# Automaton_no_switches.net
KiCad netlist of a schematic drawn in EAGLE
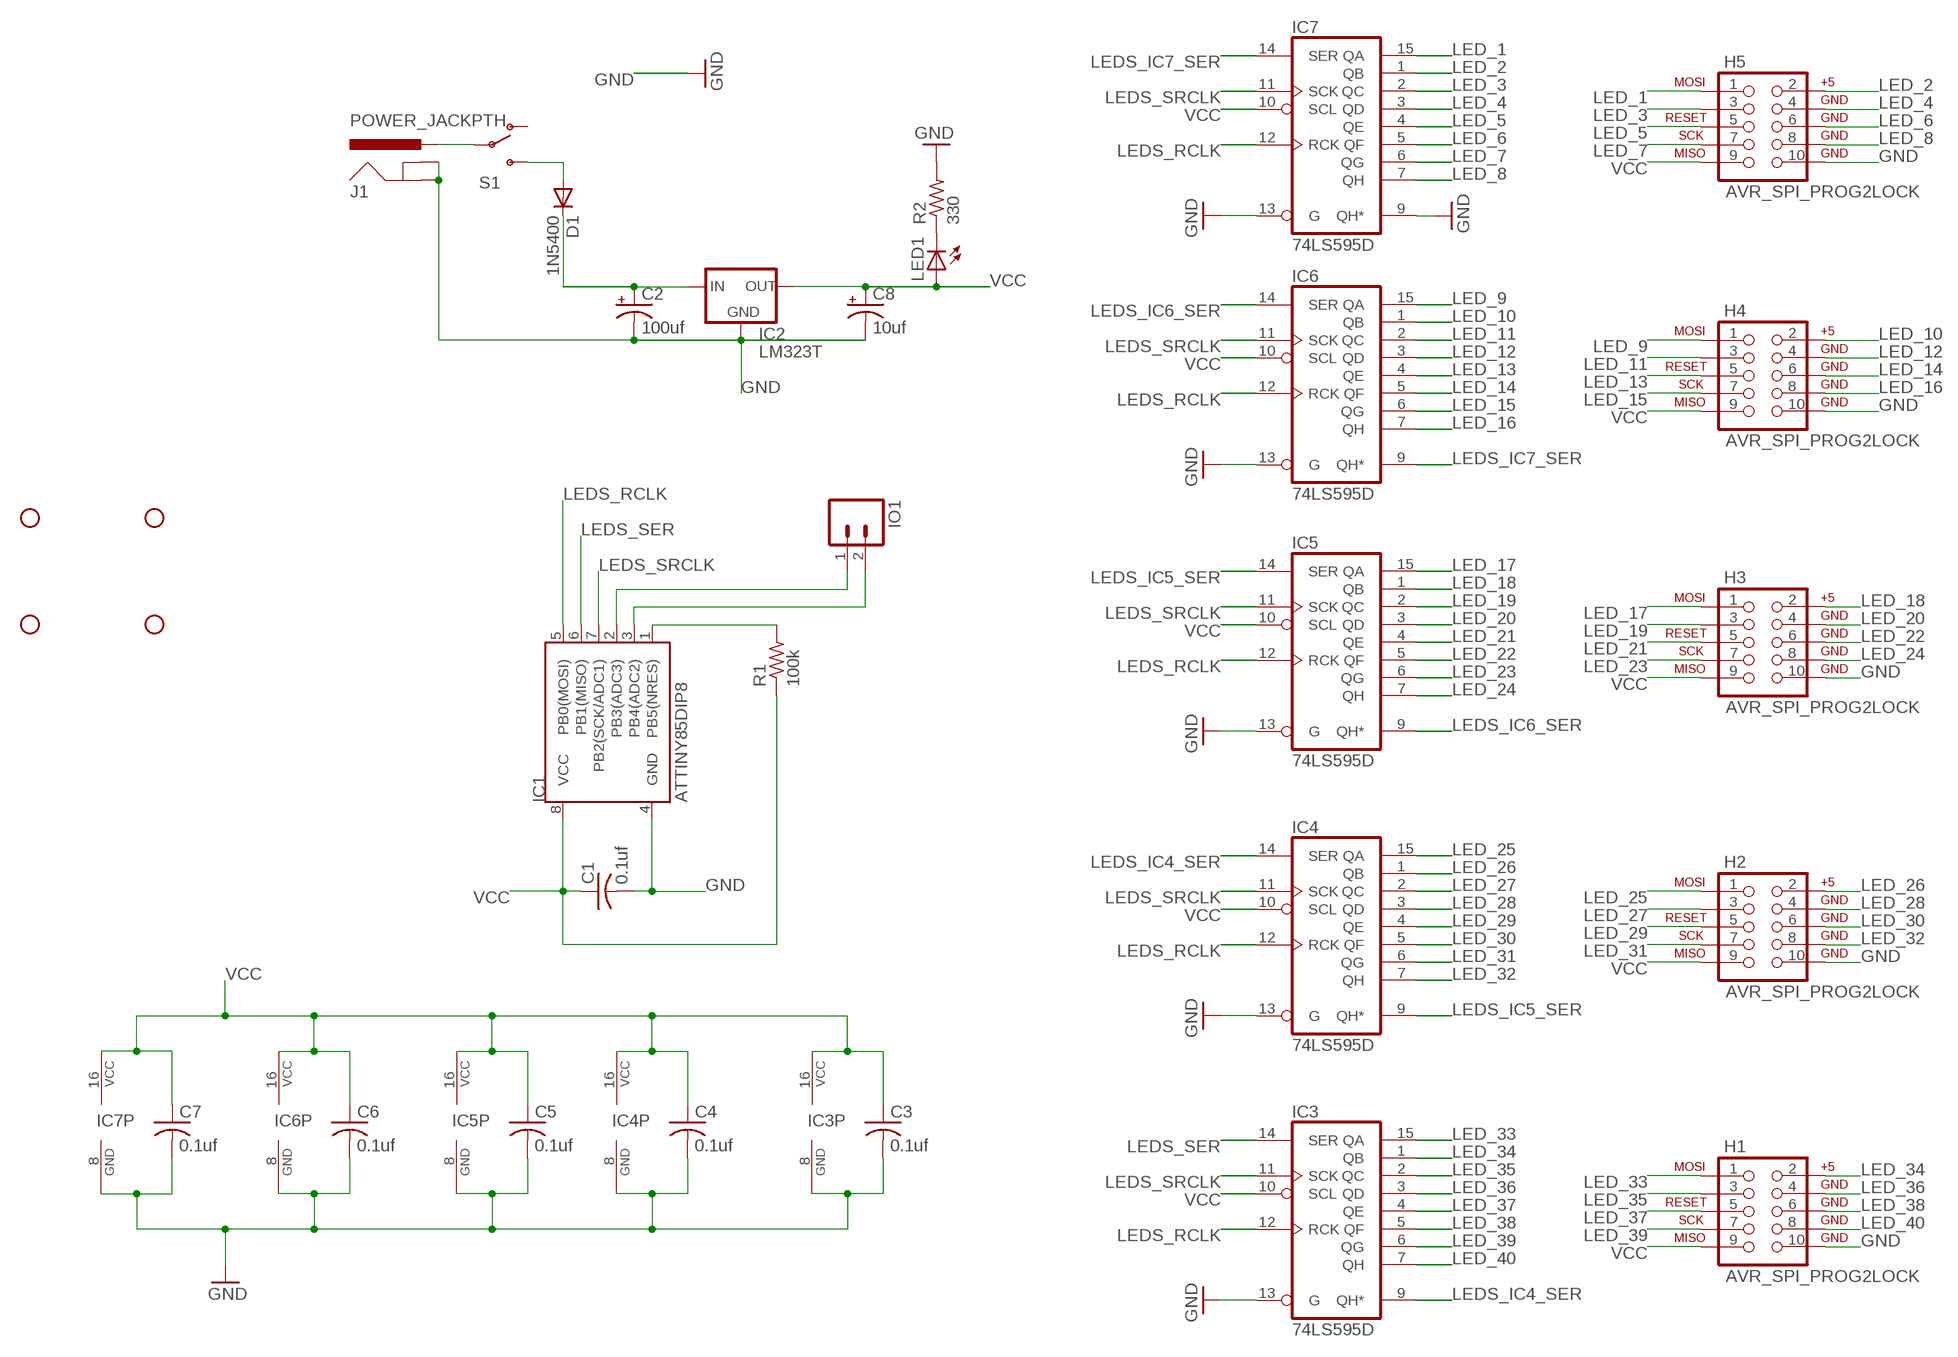
[diagram p0: schematic, sheet 1]

(export (version "E")
  (design (tool "Eeschema 10.0.6"))
  (components
    (comp (ref "C1")
      (value "0.1uf")
      (footprint "eagle-import:C1206")
      (libsource (lib "eagle-import") (part "C-USC1206"))
    )
    (comp (ref "C2")
      (value "100uf")
      (footprint "eagle-import:E5-10,5")
      (libsource (lib "eagle-import") (part "CPOL-USE5-10.5"))
    )
    (comp (ref "C3")
      (value "0.1uf")
      (footprint "eagle-import:C1206")
      (libsource (lib "eagle-import") (part "C-USC1206"))
    )
    (comp (ref "C4")
      (value "0.1uf")
      (footprint "eagle-import:C1206")
      (libsource (lib "eagle-import") (part "C-USC1206"))
    )
    (comp (ref "C5")
      (value "0.1uf")
      (footprint "eagle-import:C1206")
      (libsource (lib "eagle-import") (part "C-USC1206"))
    )
    (comp (ref "C6")
      (value "0.1uf")
      (footprint "eagle-import:C1206")
      (libsource (lib "eagle-import") (part "C-USC1206"))
    )
    (comp (ref "C7")
      (value "0.1uf")
      (footprint "eagle-import:C1206")
      (libsource (lib "eagle-import") (part "C-USC1206"))
    )
    (comp (ref "C8")
      (value "10uf")
      (footprint "eagle-import:E2-5")
      (libsource (lib "eagle-import") (part "CPOL-USE2-5"))
    )
    (comp (ref "D1")
      (value "1N5400")
      (footprint "eagle-import:DO201-15")
      (libsource (lib "eagle-import") (part "1N5400"))
    )
    (comp (ref "H1")
      (value "AVR_SPI_PROG2LOCK")
      (footprint "eagle-import:2X5-SHROUDED_LOCK")
      (libsource (lib "eagle-import") (part "AVR_SPI_PROG2LOCK"))
    )
    (comp (ref "H2")
      (value "AVR_SPI_PROG2LOCK")
      (footprint "eagle-import:2X5-SHROUDED_LOCK")
      (libsource (lib "eagle-import") (part "AVR_SPI_PROG2LOCK"))
    )
    (comp (ref "H3")
      (value "AVR_SPI_PROG2LOCK")
      (footprint "eagle-import:2X5-SHROUDED_LOCK")
      (libsource (lib "eagle-import") (part "AVR_SPI_PROG2LOCK"))
    )
    (comp (ref "H4")
      (value "AVR_SPI_PROG2LOCK")
      (footprint "eagle-import:2X5-SHROUDED_LOCK")
      (libsource (lib "eagle-import") (part "AVR_SPI_PROG2LOCK"))
    )
    (comp (ref "H5")
      (value "AVR_SPI_PROG2LOCK")
      (footprint "eagle-import:2X5-SHROUDED_LOCK")
      (libsource (lib "eagle-import") (part "AVR_SPI_PROG2LOCK"))
    )
    (comp (ref "HOLE1")
      (value "STAND-OFF")
      (footprint "eagle-import:STAND-OFF")
      (libsource (lib "eagle-import") (part "STAND-OFF"))
    )
    (comp (ref "HOLE2")
      (value "STAND-OFF")
      (footprint "eagle-import:STAND-OFF")
      (libsource (lib "eagle-import") (part "STAND-OFF"))
    )
    (comp (ref "HOLE3")
      (value "STAND-OFF")
      (footprint "eagle-import:STAND-OFF")
      (libsource (lib "eagle-import") (part "STAND-OFF"))
    )
    (comp (ref "HOLE4")
      (value "STAND-OFF")
      (footprint "eagle-import:STAND-OFF")
      (libsource (lib "eagle-import") (part "STAND-OFF"))
    )
    (comp (ref "IC1")
      (value "ATTINY85DIP8")
      (footprint "eagle-import:DIP08")
      (libsource (lib "eagle-import") (part "ATTINY85DIP8"))
    )
    (comp (ref "IC2")
      (value "LM323T")
      (footprint "eagle-import:TO220-IGO")
      (libsource (lib "eagle-import") (part "V_REG_78XXSINK"))
    )
    (comp (ref "IC3")
      (value "74LS595D")
      (footprint "eagle-import:SO16")
      (libsource (lib "eagle-import") (part "74595DLS"))
    )
    (comp (ref "IC4")
      (value "74LS595D")
      (footprint "eagle-import:SO16")
      (libsource (lib "eagle-import") (part "74595DLS"))
    )
    (comp (ref "IC5")
      (value "74LS595D")
      (footprint "eagle-import:SO16")
      (libsource (lib "eagle-import") (part "74595DLS"))
    )
    (comp (ref "IC6")
      (value "74LS595D")
      (footprint "eagle-import:SO16")
      (libsource (lib "eagle-import") (part "74595DLS"))
    )
    (comp (ref "IC7")
      (value "74LS595D")
      (footprint "eagle-import:SO16")
      (libsource (lib "eagle-import") (part "74595DLS"))
    )
    (comp (ref "IO1")
      (value "M02PTH3")
      (footprint "eagle-import:1X02_LONGPADS")
      (libsource (lib "eagle-import") (part "M02PTH3"))
    )
    (comp (ref "J1")
      (value "POWER_JACKPTH")
      (footprint "eagle-import:POWER_JACK_PTH")
      (libsource (lib "eagle-import") (part "POWER_JACKPTH"))
    )
    (comp (ref "LED1")
      (value "LEDSMT1206")
      (footprint "eagle-import:1206")
      (libsource (lib "eagle-import") (part "LEDSMT1206"))
    )
    (comp (ref "R1")
      (value "100k")
      (footprint "eagle-import:M1206")
      (libsource (lib "eagle-import") (part "R-US_M1206"))
    )
    (comp (ref "R2")
      (value "330")
      (footprint "eagle-import:M1206")
      (libsource (lib "eagle-import") (part "R-US_M1206"))
    )
    (comp (ref "S1")
      (value "SWITCH-SPDTPTH_LOCK")
      (footprint "eagle-import:SWITCH-SPDT_LOCK.007S")
      (libsource (lib "eagle-import") (part "SWITCH-SPDTPTH_LOCK"))
    )
  )
  (nets
    (net (code "1") (name "/LEDS_IC4_SER") (class "Default")
      (node (ref "IC3") (pin "9") (pinfunction "QH*_9") (pintype "tri_state"))
      (node (ref "IC4") (pin "14") (pinfunction "SER_14") (pintype "input"))
    )
    (net (code "2") (name "/LEDS_IC5_SER") (class "Default")
      (node (ref "IC4") (pin "9") (pinfunction "QH*_9") (pintype "tri_state"))
      (node (ref "IC5") (pin "14") (pinfunction "SER_14") (pintype "input"))
    )
    (net (code "3") (name "/LEDS_IC6_SER") (class "Default")
      (node (ref "IC5") (pin "9") (pinfunction "QH*_9") (pintype "tri_state"))
      (node (ref "IC6") (pin "14") (pinfunction "SER_14") (pintype "input"))
    )
    (net (code "4") (name "/LEDS_IC7_SER") (class "Default")
      (node (ref "IC6") (pin "9") (pinfunction "QH*_9") (pintype "tri_state"))
      (node (ref "IC7") (pin "14") (pinfunction "SER_14") (pintype "input"))
    )
    (net (code "5") (name "/LEDS_RCLK") (class "Default")
      (node (ref "IC1") (pin "5") (pinfunction "PB0(MOSI)_5") (pintype "bidirectional"))
      (node (ref "IC3") (pin "12") (pinfunction "RCK_12") (pintype "input"))
      (node (ref "IC4") (pin "12") (pinfunction "RCK_12") (pintype "input"))
      (node (ref "IC5") (pin "12") (pinfunction "RCK_12") (pintype "input"))
      (node (ref "IC6") (pin "12") (pinfunction "RCK_12") (pintype "input"))
      (node (ref "IC7") (pin "12") (pinfunction "RCK_12") (pintype "input"))
    )
    (net (code "6") (name "/LEDS_SER") (class "Default")
      (node (ref "IC1") (pin "6") (pinfunction "PB1(MISO)_6") (pintype "bidirectional"))
      (node (ref "IC3") (pin "14") (pinfunction "SER_14") (pintype "input"))
    )
    (net (code "7") (name "/LEDS_SRCLK") (class "Default")
      (node (ref "IC1") (pin "7") (pinfunction "PB2(SCK/ADC1)_7") (pintype "bidirectional"))
      (node (ref "IC3") (pin "11") (pinfunction "SCK_11") (pintype "input"))
      (node (ref "IC4") (pin "11") (pinfunction "SCK_11") (pintype "input"))
      (node (ref "IC5") (pin "11") (pinfunction "SCK_11") (pintype "input"))
      (node (ref "IC6") (pin "11") (pinfunction "SCK_11") (pintype "input"))
      (node (ref "IC7") (pin "11") (pinfunction "SCK_11") (pintype "input"))
    )
    (net (code "8") (name "/LED_1") (class "Default")
      (node (ref "H5") (pin "1") (pinfunction "1_1") (pintype "passive"))
      (node (ref "IC7") (pin "15") (pinfunction "QA_15") (pintype "tri_state"))
    )
    (net (code "9") (name "/LED_2") (class "Default")
      (node (ref "H5") (pin "2") (pinfunction "2_2") (pintype "passive"))
      (node (ref "IC7") (pin "1") (pinfunction "QB_1") (pintype "tri_state"))
    )
    (net (code "10") (name "/LED_3") (class "Default")
      (node (ref "H5") (pin "3") (pinfunction "3_3") (pintype "passive"))
      (node (ref "IC7") (pin "2") (pinfunction "QC_2") (pintype "tri_state"))
    )
    (net (code "11") (name "/LED_4") (class "Default")
      (node (ref "H5") (pin "4") (pinfunction "4_4") (pintype "passive"))
      (node (ref "IC7") (pin "3") (pinfunction "QD_3") (pintype "tri_state"))
    )
    (net (code "12") (name "/LED_5") (class "Default")
      (node (ref "H5") (pin "5") (pinfunction "5_5") (pintype "passive"))
      (node (ref "IC7") (pin "4") (pinfunction "QE_4") (pintype "tri_state"))
    )
    (net (code "13") (name "/LED_6") (class "Default")
      (node (ref "H5") (pin "6") (pinfunction "6_6") (pintype "passive"))
      (node (ref "IC7") (pin "5") (pinfunction "QF_5") (pintype "tri_state"))
    )
    (net (code "14") (name "/LED_7") (class "Default")
      (node (ref "H5") (pin "7") (pinfunction "7_7") (pintype "passive"))
      (node (ref "IC7") (pin "6") (pinfunction "QG_6") (pintype "tri_state"))
    )
    (net (code "15") (name "/LED_8") (class "Default")
      (node (ref "H5") (pin "8") (pinfunction "8_8") (pintype "passive"))
      (node (ref "IC7") (pin "7") (pinfunction "QH_7") (pintype "tri_state"))
    )
    (net (code "16") (name "/LED_9") (class "Default")
      (node (ref "H4") (pin "1") (pinfunction "1_1") (pintype "passive"))
      (node (ref "IC6") (pin "15") (pinfunction "QA_15") (pintype "tri_state"))
    )
    (net (code "17") (name "/LED_10") (class "Default")
      (node (ref "H4") (pin "2") (pinfunction "2_2") (pintype "passive"))
      (node (ref "IC6") (pin "1") (pinfunction "QB_1") (pintype "tri_state"))
    )
    (net (code "18") (name "/LED_11") (class "Default")
      (node (ref "H4") (pin "3") (pinfunction "3_3") (pintype "passive"))
      (node (ref "IC6") (pin "2") (pinfunction "QC_2") (pintype "tri_state"))
    )
    (net (code "19") (name "/LED_12") (class "Default")
      (node (ref "H4") (pin "4") (pinfunction "4_4") (pintype "passive"))
      (node (ref "IC6") (pin "3") (pinfunction "QD_3") (pintype "tri_state"))
    )
    (net (code "20") (name "/LED_13") (class "Default")
      (node (ref "H4") (pin "5") (pinfunction "5_5") (pintype "passive"))
      (node (ref "IC6") (pin "4") (pinfunction "QE_4") (pintype "tri_state"))
    )
    (net (code "21") (name "/LED_14") (class "Default")
      (node (ref "H4") (pin "6") (pinfunction "6_6") (pintype "passive"))
      (node (ref "IC6") (pin "5") (pinfunction "QF_5") (pintype "tri_state"))
    )
    (net (code "22") (name "/LED_15") (class "Default")
      (node (ref "H4") (pin "7") (pinfunction "7_7") (pintype "passive"))
      (node (ref "IC6") (pin "6") (pinfunction "QG_6") (pintype "tri_state"))
    )
    (net (code "23") (name "/LED_16") (class "Default")
      (node (ref "H4") (pin "8") (pinfunction "8_8") (pintype "passive"))
      (node (ref "IC6") (pin "7") (pinfunction "QH_7") (pintype "tri_state"))
    )
    (net (code "24") (name "/LED_17") (class "Default")
      (node (ref "H3") (pin "1") (pinfunction "1_1") (pintype "passive"))
      (node (ref "IC5") (pin "15") (pinfunction "QA_15") (pintype "tri_state"))
    )
    (net (code "25") (name "/LED_18") (class "Default")
      (node (ref "H3") (pin "2") (pinfunction "2_2") (pintype "passive"))
      (node (ref "IC5") (pin "1") (pinfunction "QB_1") (pintype "tri_state"))
    )
    (net (code "26") (name "/LED_19") (class "Default")
      (node (ref "H3") (pin "3") (pinfunction "3_3") (pintype "passive"))
      (node (ref "IC5") (pin "2") (pinfunction "QC_2") (pintype "tri_state"))
    )
    (net (code "27") (name "/LED_20") (class "Default")
      (node (ref "H3") (pin "4") (pinfunction "4_4") (pintype "passive"))
      (node (ref "IC5") (pin "3") (pinfunction "QD_3") (pintype "tri_state"))
    )
    (net (code "28") (name "/LED_21") (class "Default")
      (node (ref "H3") (pin "5") (pinfunction "5_5") (pintype "passive"))
      (node (ref "IC5") (pin "4") (pinfunction "QE_4") (pintype "tri_state"))
    )
    (net (code "29") (name "/LED_22") (class "Default")
      (node (ref "H3") (pin "6") (pinfunction "6_6") (pintype "passive"))
      (node (ref "IC5") (pin "5") (pinfunction "QF_5") (pintype "tri_state"))
    )
    (net (code "30") (name "/LED_23") (class "Default")
      (node (ref "H3") (pin "7") (pinfunction "7_7") (pintype "passive"))
      (node (ref "IC5") (pin "6") (pinfunction "QG_6") (pintype "tri_state"))
    )
    (net (code "31") (name "/LED_24") (class "Default")
      (node (ref "H3") (pin "8") (pinfunction "8_8") (pintype "passive"))
      (node (ref "IC5") (pin "7") (pinfunction "QH_7") (pintype "tri_state"))
    )
    (net (code "32") (name "/LED_25") (class "Default")
      (node (ref "H2") (pin "1") (pinfunction "1_1") (pintype "passive"))
      (node (ref "IC4") (pin "15") (pinfunction "QA_15") (pintype "tri_state"))
    )
    (net (code "33") (name "/LED_26") (class "Default")
      (node (ref "H2") (pin "2") (pinfunction "2_2") (pintype "passive"))
      (node (ref "IC4") (pin "1") (pinfunction "QB_1") (pintype "tri_state"))
    )
    (net (code "34") (name "/LED_27") (class "Default")
      (node (ref "H2") (pin "3") (pinfunction "3_3") (pintype "passive"))
      (node (ref "IC4") (pin "2") (pinfunction "QC_2") (pintype "tri_state"))
    )
    (net (code "35") (name "/LED_28") (class "Default")
      (node (ref "H2") (pin "4") (pinfunction "4_4") (pintype "passive"))
      (node (ref "IC4") (pin "3") (pinfunction "QD_3") (pintype "tri_state"))
    )
    (net (code "36") (name "/LED_29") (class "Default")
      (node (ref "H2") (pin "5") (pinfunction "5_5") (pintype "passive"))
      (node (ref "IC4") (pin "4") (pinfunction "QE_4") (pintype "tri_state"))
    )
    (net (code "37") (name "/LED_30") (class "Default")
      (node (ref "H2") (pin "6") (pinfunction "6_6") (pintype "passive"))
      (node (ref "IC4") (pin "5") (pinfunction "QF_5") (pintype "tri_state"))
    )
    (net (code "38") (name "/LED_31") (class "Default")
      (node (ref "H2") (pin "7") (pinfunction "7_7") (pintype "passive"))
      (node (ref "IC4") (pin "6") (pinfunction "QG_6") (pintype "tri_state"))
    )
    (net (code "39") (name "/LED_32") (class "Default")
      (node (ref "H2") (pin "8") (pinfunction "8_8") (pintype "passive"))
      (node (ref "IC4") (pin "7") (pinfunction "QH_7") (pintype "tri_state"))
    )
    (net (code "40") (name "/LED_33") (class "Default")
      (node (ref "H1") (pin "1") (pinfunction "1_1") (pintype "passive"))
      (node (ref "IC3") (pin "15") (pinfunction "QA_15") (pintype "tri_state"))
    )
    (net (code "41") (name "/LED_34") (class "Default")
      (node (ref "H1") (pin "2") (pinfunction "2_2") (pintype "passive"))
      (node (ref "IC3") (pin "1") (pinfunction "QB_1") (pintype "tri_state"))
    )
    (net (code "42") (name "/LED_35") (class "Default")
      (node (ref "H1") (pin "3") (pinfunction "3_3") (pintype "passive"))
      (node (ref "IC3") (pin "2") (pinfunction "QC_2") (pintype "tri_state"))
    )
    (net (code "43") (name "/LED_36") (class "Default")
      (node (ref "H1") (pin "4") (pinfunction "4_4") (pintype "passive"))
      (node (ref "IC3") (pin "3") (pinfunction "QD_3") (pintype "tri_state"))
    )
    (net (code "44") (name "/LED_37") (class "Default")
      (node (ref "H1") (pin "5") (pinfunction "5_5") (pintype "passive"))
      (node (ref "IC3") (pin "4") (pinfunction "QE_4") (pintype "tri_state"))
    )
    (net (code "45") (name "/LED_38") (class "Default")
      (node (ref "H1") (pin "6") (pinfunction "6_6") (pintype "passive"))
      (node (ref "IC3") (pin "5") (pinfunction "QF_5") (pintype "tri_state"))
    )
    (net (code "46") (name "/LED_39") (class "Default")
      (node (ref "H1") (pin "7") (pinfunction "7_7") (pintype "passive"))
      (node (ref "IC3") (pin "6") (pinfunction "QG_6") (pintype "tri_state"))
    )
    (net (code "47") (name "/LED_40") (class "Default")
      (node (ref "H1") (pin "8") (pinfunction "8_8") (pintype "passive"))
      (node (ref "IC3") (pin "7") (pinfunction "QH_7") (pintype "tri_state"))
    )
    (net (code "48") (name "/VCC") (class "Default")
      (node (ref "C1") (pin "1") (pinfunction "1_1") (pintype "passive"))
      (node (ref "C3") (pin "1") (pinfunction "1_1") (pintype "passive"))
      (node (ref "C4") (pin "1") (pinfunction "1_1") (pintype "passive"))
      (node (ref "C5") (pin "1") (pinfunction "1_1") (pintype "passive"))
      (node (ref "C6") (pin "1") (pinfunction "1_1") (pintype "passive"))
      (node (ref "C7") (pin "1") (pinfunction "1_1") (pintype "passive"))
      (node (ref "C8") (pin "+") (pinfunction "+_+") (pintype "passive"))
      (node (ref "H1") (pin "9") (pinfunction "9_9") (pintype "passive"))
      (node (ref "H2") (pin "9") (pinfunction "9_9") (pintype "passive"))
      (node (ref "H3") (pin "9") (pinfunction "9_9") (pintype "passive"))
      (node (ref "H4") (pin "9") (pinfunction "9_9") (pintype "passive"))
      (node (ref "H5") (pin "9") (pinfunction "9_9") (pintype "passive"))
      (node (ref "IC1") (pin "8") (pinfunction "VCC_8") (pintype "bidirectional"))
      (node (ref "IC2") (pin "OUT") (pinfunction "OUT_OUT") (pintype "output"))
      (node (ref "IC3") (pin "10") (pinfunction "SCL_10") (pintype "input"))
      (node (ref "IC3") (pin "16") (pinfunction "VCC_16") (pintype "power_in"))
      (node (ref "IC4") (pin "10") (pinfunction "SCL_10") (pintype "input"))
      (node (ref "IC4") (pin "16") (pinfunction "VCC_16") (pintype "power_in"))
      (node (ref "IC5") (pin "10") (pinfunction "SCL_10") (pintype "input"))
      (node (ref "IC5") (pin "16") (pinfunction "VCC_16") (pintype "power_in"))
      (node (ref "IC6") (pin "10") (pinfunction "SCL_10") (pintype "input"))
      (node (ref "IC6") (pin "16") (pinfunction "VCC_16") (pintype "power_in"))
      (node (ref "IC7") (pin "10") (pinfunction "SCL_10") (pintype "input"))
      (node (ref "IC7") (pin "16") (pinfunction "VCC_16") (pintype "power_in"))
      (node (ref "LED1") (pin "A") (pinfunction "A_A") (pintype "passive"))
      (node (ref "R1") (pin "1") (pinfunction "1_1") (pintype "passive"))
    )
    (net (code "49") (name "GND") (class "Default")
      (node (ref "C1") (pin "2") (pinfunction "2_2") (pintype "passive"))
      (node (ref "C2") (pin "-") (pinfunction "-_-") (pintype "passive"))
      (node (ref "C3") (pin "2") (pinfunction "2_2") (pintype "passive"))
      (node (ref "C4") (pin "2") (pinfunction "2_2") (pintype "passive"))
      (node (ref "C5") (pin "2") (pinfunction "2_2") (pintype "passive"))
      (node (ref "C6") (pin "2") (pinfunction "2_2") (pintype "passive"))
      (node (ref "C7") (pin "2") (pinfunction "2_2") (pintype "passive"))
      (node (ref "C8") (pin "-") (pinfunction "-_-") (pintype "passive"))
      (node (ref "H1") (pin "10") (pinfunction "10_10") (pintype "passive"))
      (node (ref "H2") (pin "10") (pinfunction "10_10") (pintype "passive"))
      (node (ref "H3") (pin "10") (pinfunction "10_10") (pintype "passive"))
      (node (ref "H4") (pin "10") (pinfunction "10_10") (pintype "passive"))
      (node (ref "H5") (pin "10") (pinfunction "10_10") (pintype "passive"))
      (node (ref "IC1") (pin "4") (pinfunction "GND_4") (pintype "bidirectional"))
      (node (ref "IC2") (pin "GND") (pinfunction "GND_GND") (pintype "input"))
      (node (ref "IC3") (pin "13") (pinfunction "G_13") (pintype "input"))
      (node (ref "IC3") (pin "8") (pinfunction "GND_8") (pintype "power_in"))
      (node (ref "IC4") (pin "13") (pinfunction "G_13") (pintype "input"))
      (node (ref "IC4") (pin "8") (pinfunction "GND_8") (pintype "power_in"))
      (node (ref "IC5") (pin "13") (pinfunction "G_13") (pintype "input"))
      (node (ref "IC5") (pin "8") (pinfunction "GND_8") (pintype "power_in"))
      (node (ref "IC6") (pin "13") (pinfunction "G_13") (pintype "input"))
      (node (ref "IC6") (pin "8") (pinfunction "GND_8") (pintype "power_in"))
      (node (ref "IC7") (pin "13") (pinfunction "G_13") (pintype "input"))
      (node (ref "IC7") (pin "8") (pinfunction "GND_8") (pintype "power_in"))
      (node (ref "IC7") (pin "9") (pinfunction "QH*_9") (pintype "tri_state"))
      (node (ref "J1") (pin "GND") (pinfunction "GND_GND") (pintype "bidirectional"))
      (node (ref "J1") (pin "GNDBREAK") (pinfunction "GNDBREAK_GNDBREAK") (pintype "bidirectional"))
      (node (ref "R2") (pin "2") (pinfunction "2_2") (pintype "passive"))
    )
    (net (code "50") (name "Net-(C2-Pad+)") (class "Default")
      (node (ref "C2") (pin "+") (pinfunction "+_+") (pintype "passive"))
      (node (ref "D1") (pin "C") (pinfunction "C_C") (pintype "passive"))
      (node (ref "IC2") (pin "IN") (pinfunction "IN_IN") (pintype "input"))
    )
    (net (code "51") (name "Net-(IC1-PB3(ADC3))") (class "Default")
      (node (ref "IC1") (pin "2") (pinfunction "PB3(ADC3)_2") (pintype "bidirectional"))
      (node (ref "IO1") (pin "1") (pinfunction "1_1") (pintype "passive"))
    )
    (net (code "52") (name "Net-(IC1-PB4(ADC2))") (class "Default")
      (node (ref "IC1") (pin "3") (pinfunction "PB4(ADC2)_3") (pintype "bidirectional"))
      (node (ref "IO1") (pin "2") (pinfunction "2_2") (pintype "passive"))
    )
    (net (code "53") (name "Net-(IC1-PB5(NRES))") (class "Default")
      (node (ref "IC1") (pin "1") (pinfunction "PB5(NRES)_1") (pintype "bidirectional"))
      (node (ref "R1") (pin "2") (pinfunction "2_2") (pintype "passive"))
    )
    (net (code "54") (name "Net-(LED1-PadC)") (class "Default")
      (node (ref "LED1") (pin "C") (pinfunction "C_C") (pintype "passive"))
      (node (ref "R2") (pin "1") (pinfunction "1_1") (pintype "passive"))
    )
    (net (code "55") (name "Net-(S1-P)") (class "Default")
      (node (ref "J1") (pin "PWR") (pinfunction "PWR_PWR") (pintype "bidirectional"))
      (node (ref "S1") (pin "2") (pinfunction "P_2") (pintype "passive"))
    )
    (net (code "56") (name "Net-(S1-S)") (class "Default")
      (node (ref "D1") (pin "A") (pinfunction "A_A") (pintype "passive"))
      (node (ref "S1") (pin "3") (pinfunction "S_3") (pintype "passive"))
    )
    (net (code "57") (name "unconnected-(S1-O-Pad1)") (class "Default")
      (node (ref "S1") (pin "1") (pinfunction "O_1") (pintype "passive"))
    )
  )
)
